# NIXIE_3.net
KiCad netlist of a schematic drawn in Altium Designer
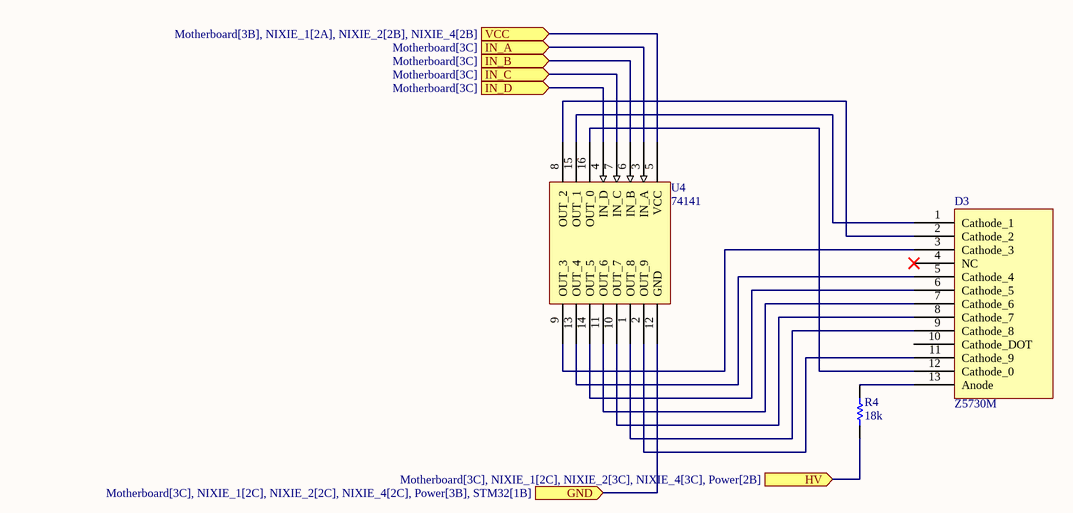
[diagram p0: NIXIE_3.SchDoc]

(export (version "E")
  (design (tool "Eeschema 10.0.6"))
  (components
    (comp (ref "D3") (value "Z5730M") (footprint "Z5730M") (libsource (lib "Z5730M") (part "Z5730M")))
    (comp (ref "R4")
      (value "18k")
      (footprint "RESC2013X60X40LL20T25")
      (fields (field (name "MANUFACTURER") "Panasonic") (field (name "PART NUMBER") "ERA6AEB183V"))
      (libsource (lib "Altium Content Vault") (part "RES"))
    )
    (comp (ref "U4") (value "74141") (footprint "DIP-16") (libsource (lib "Z5730M") (part "74141")))
  )
  (nets
    (net (code "1") (name "/GND") (class "Default")
      (node (ref "U4") (pin "12") (pinfunction "GND_12") (pintype "power_in"))
    )
    (net (code "2") (name "/HV") (class "Default")
      (node (ref "R4") (pin "1") (pinfunction "1_1") (pintype "passive"))
    )
    (net (code "3") (name "/IN_A") (class "Default")
      (node (ref "U4") (pin "3") (pinfunction "IN_A_3") (pintype "input"))
    )
    (net (code "4") (name "/IN_B") (class "Default")
      (node (ref "U4") (pin "6") (pinfunction "IN_B_6") (pintype "input"))
    )
    (net (code "5") (name "/IN_C") (class "Default")
      (node (ref "U4") (pin "7") (pinfunction "IN_C_7") (pintype "input"))
    )
    (net (code "6") (name "/IN_D") (class "Default")
      (node (ref "U4") (pin "4") (pinfunction "IN_D_4") (pintype "input"))
    )
    (net (code "7") (name "/VCC") (class "Default")
      (node (ref "U4") (pin "5") (pinfunction "VCC_5") (pintype "power_in"))
    )
    (net (code "8") (name "Net-(D3-Anode)") (class "Default")
      (node (ref "D3") (pin "13") (pinfunction "Anode_13") (pintype "passive"))
      (node (ref "R4") (pin "2") (pinfunction "2_2") (pintype "passive"))
    )
    (net (code "9") (name "Net-(D3-Cathode_0)") (class "Default")
      (node (ref "D3") (pin "12") (pinfunction "Cathode_0_12") (pintype "passive"))
      (node (ref "U4") (pin "16") (pinfunction "OUT_0_16") (pintype "open_collector"))
    )
    (net (code "10") (name "Net-(D3-Cathode_1)") (class "Default")
      (node (ref "D3") (pin "1") (pinfunction "Cathode_1_1") (pintype "passive"))
      (node (ref "U4") (pin "15") (pinfunction "OUT_1_15") (pintype "open_collector"))
    )
    (net (code "11") (name "Net-(D3-Cathode_2)") (class "Default")
      (node (ref "D3") (pin "2") (pinfunction "Cathode_2_2") (pintype "passive"))
      (node (ref "U4") (pin "8") (pinfunction "OUT_2_8") (pintype "open_collector"))
    )
    (net (code "12") (name "Net-(D3-Cathode_3)") (class "Default")
      (node (ref "D3") (pin "3") (pinfunction "Cathode_3_3") (pintype "passive"))
      (node (ref "U4") (pin "9") (pinfunction "OUT_3_9") (pintype "open_collector"))
    )
    (net (code "13") (name "Net-(D3-Cathode_4)") (class "Default")
      (node (ref "D3") (pin "5") (pinfunction "Cathode_4_5") (pintype "passive"))
      (node (ref "U4") (pin "13") (pinfunction "OUT_4_13") (pintype "open_collector"))
    )
    (net (code "14") (name "Net-(D3-Cathode_5)") (class "Default")
      (node (ref "D3") (pin "6") (pinfunction "Cathode_5_6") (pintype "passive"))
      (node (ref "U4") (pin "14") (pinfunction "OUT_5_14") (pintype "open_collector"))
    )
    (net (code "15") (name "Net-(D3-Cathode_6)") (class "Default")
      (node (ref "D3") (pin "7") (pinfunction "Cathode_6_7") (pintype "passive"))
      (node (ref "U4") (pin "11") (pinfunction "OUT_6_11") (pintype "open_collector"))
    )
    (net (code "16") (name "Net-(D3-Cathode_7)") (class "Default")
      (node (ref "D3") (pin "8") (pinfunction "Cathode_7_8") (pintype "passive"))
      (node (ref "U4") (pin "10") (pinfunction "OUT_7_10") (pintype "open_collector"))
    )
    (net (code "17") (name "Net-(D3-Cathode_8)") (class "Default")
      (node (ref "D3") (pin "9") (pinfunction "Cathode_8_9") (pintype "passive"))
      (node (ref "U4") (pin "1") (pinfunction "OUT_8_1") (pintype "open_collector"))
    )
    (net (code "18") (name "Net-(D3-Cathode_9)") (class "Default")
      (node (ref "D3") (pin "11") (pinfunction "Cathode_9_11") (pintype "passive"))
      (node (ref "U4") (pin "2") (pinfunction "OUT_9_2") (pintype "open_collector"))
    )
    (net (code "19") (name "unconnected-(D3-Cathode_DOT-Pad10)") (class "Default")
      (node (ref "D3") (pin "10") (pinfunction "Cathode_DOT_10") (pintype "passive"))
    )
    (net (code "20") (name "unconnected-(D3-NC-Pad4)") (class "Default")
      (node (ref "D3") (pin "4") (pinfunction "NC_4") (pintype "passive+no_connect"))
    )
  )
)
